# Connector_USB-C_TH_USB2_0.net
KiCad netlist of a schematic drawn in Altium Designer
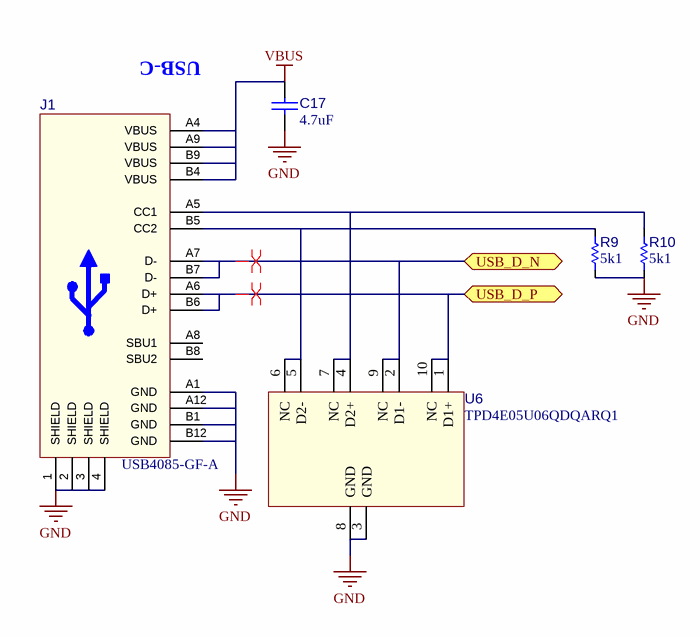
[diagram p0: Connector USB-C TH USB2.0.SchDoc]

(export (version "E")
  (design (tool "Eeschema 10.0.6"))
  (components
    (comp (ref "C17")
      (value "4.7uF")
      (footprint "C_2012[0805]")
      (description "Capacitor type 1")
      (fields (field (name "TOLERANCE") "10%") (field (name "Comment") "Cap 4.7uF 0805"))
      (libsource (lib "TEP_243-Altium_DBLib") (part "capacitor"))
    )
    (comp (ref "J1")
      (value "USB4085-GF-A")
      (footprint "FP-USB4085-GF-A-MFG")
      (description "CONN RCPT USB2.0 TYPE C RA - TH")
      (libsource (lib "243-336_MP_Manette") (part "J_USB-C_16pos"))
    )
    (comp (ref "R9")
      (value "5k1")
      (footprint "R_1005[0402]")
      (description "Resistor type 1")
      (fields (field (name "TOLERANCE") "1%") (field (name "Comment") "Res 5k1 1% 0402"))
      (libsource (lib "TEP_243-Altium_DBLib") (part "resistor"))
    )
    (comp (ref "R10")
      (value "5k1")
      (footprint "R_1005[0402]")
      (description "Resistor type 1")
      (fields (field (name "TOLERANCE") "1%") (field (name "Comment") "Res 5k1 1% 0402"))
      (libsource (lib "TEP_243-Altium_DBLib") (part "resistor"))
    )
    (comp (ref "U6")
      (value "TPD4E05U06QDQARQ1")
      (footprint "U_USON50P250X100-10")
      (description "TVS DIODE 5.5V 14V 10USON")
      (libsource (lib "243-336_MP_Manette") (part "U_TPD4E05U06"))
    )
  )
  (nets
    (net (code "1") (name "/USB_D_N") (class "Default")
      (node (ref "J1") (pin "A7") (pinfunction "D-_A7") (pintype "passive"))
      (node (ref "J1") (pin "B7") (pinfunction "D-_B7") (pintype "passive"))
      (node (ref "U6") (pin "2") (pinfunction "D1-_2") (pintype "passive"))
      (node (ref "U6") (pin "9") (pinfunction "NC_9") (pintype "passive"))
    )
    (net (code "2") (name "/USB_D_P") (class "Default")
      (node (ref "J1") (pin "A6") (pinfunction "D+_A6") (pintype "passive"))
      (node (ref "J1") (pin "B6") (pinfunction "D+_B6") (pintype "passive"))
      (node (ref "U6") (pin "1") (pinfunction "D1+_1") (pintype "passive"))
      (node (ref "U6") (pin "10") (pinfunction "NC_10") (pintype "passive"))
    )
    (net (code "3") (name "GND") (class "Default")
      (node (ref "C17") (pin "1") (pinfunction "1_1") (pintype "passive"))
      (node (ref "J1") (pin "1") (pinfunction "SHIELD_1") (pintype "passive"))
      (node (ref "J1") (pin "2") (pinfunction "SHIELD_2") (pintype "passive"))
      (node (ref "J1") (pin "3") (pinfunction "SHIELD_3") (pintype "passive"))
      (node (ref "J1") (pin "4") (pinfunction "SHIELD_4") (pintype "passive"))
      (node (ref "J1") (pin "A1") (pinfunction "GND_A1") (pintype "passive"))
      (node (ref "J1") (pin "A12") (pinfunction "GND_A12") (pintype "passive"))
      (node (ref "J1") (pin "B1") (pinfunction "GND_B1") (pintype "passive"))
      (node (ref "J1") (pin "B12") (pinfunction "GND_B12") (pintype "passive"))
      (node (ref "R10") (pin "1") (pinfunction "1_1") (pintype "passive"))
      (node (ref "R9") (pin "1") (pinfunction "1_1") (pintype "passive"))
      (node (ref "U6") (pin "3") (pinfunction "GND_3") (pintype "power_in"))
      (node (ref "U6") (pin "8") (pinfunction "GND_8") (pintype "power_in"))
    )
    (net (code "4") (name "Net-(J1-CC1)") (class "Default")
      (node (ref "J1") (pin "A5") (pinfunction "CC1_A5") (pintype "passive"))
      (node (ref "R10") (pin "2") (pinfunction "2_2") (pintype "passive"))
      (node (ref "U6") (pin "4") (pinfunction "D2+_4") (pintype "passive"))
      (node (ref "U6") (pin "7") (pinfunction "NC_7") (pintype "passive"))
    )
    (net (code "5") (name "Net-(J1-CC2)") (class "Default")
      (node (ref "J1") (pin "B5") (pinfunction "CC2_B5") (pintype "passive"))
      (node (ref "R9") (pin "2") (pinfunction "2_2") (pintype "passive"))
      (node (ref "U6") (pin "5") (pinfunction "D2-_5") (pintype "passive"))
      (node (ref "U6") (pin "6") (pinfunction "NC_6") (pintype "passive"))
    )
    (net (code "6") (name "VBUS") (class "Default")
      (node (ref "C17") (pin "2") (pinfunction "2_2") (pintype "passive"))
      (node (ref "J1") (pin "A4") (pinfunction "VBUS_A4") (pintype "passive"))
      (node (ref "J1") (pin "A9") (pinfunction "VBUS_A9") (pintype "passive"))
      (node (ref "J1") (pin "B4") (pinfunction "VBUS_B4") (pintype "passive"))
      (node (ref "J1") (pin "B9") (pinfunction "VBUS_B9") (pintype "passive"))
    )
    (net (code "7") (name "unconnected-(J1-SBU1-PadA8)") (class "Default")
      (node (ref "J1") (pin "A8") (pinfunction "SBU1_A8") (pintype "passive"))
    )
    (net (code "8") (name "unconnected-(J1-SBU2-PadB8)") (class "Default")
      (node (ref "J1") (pin "B8") (pinfunction "SBU2_B8") (pintype "passive"))
    )
  )
)
